# con_IMU.net
KiCad netlist of a schematic drawn in EAGLE
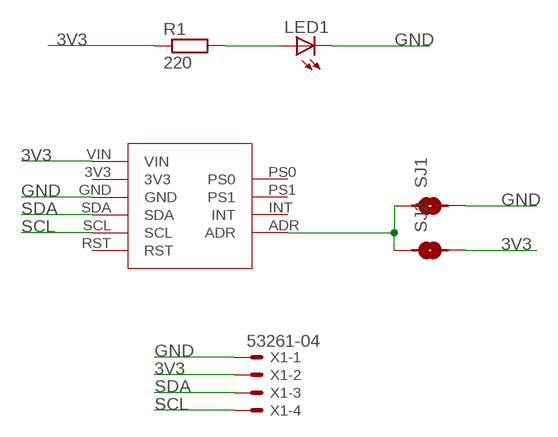
[diagram p0: schematic, sheet 1]

(export (version "E")
  (design (tool "Eeschema 10.0.6"))
  (components
    (comp (ref "LED1")
      (value "LEDCHIPLED_1206")
      (footprint "eagle-import:CHIPLED_1206")
      (libsource (lib "eagle-import") (part "LEDCHIPLED_1206"))
    )
    (comp (ref "R1")
      (value "220")
      (footprint "eagle-import:R1206")
      (libsource (lib "eagle-import") (part "RR1206"))
    )
    (comp (ref "SJ1")
      (value "SMD-JUMPER-2")
      (footprint "eagle-import:SMD-JUMPER-2")
      (libsource (lib "eagle-import") (part "SMD-JUMPER-2"))
    )
    (comp (ref "SJ2")
      (value "SMD-JUMPER-2")
      (footprint "eagle-import:SMD-JUMPER-2")
      (libsource (lib "eagle-import") (part "SMD-JUMPER-2"))
    )
    (comp (ref "U$1")
      (value "BNO055")
      (footprint "eagle-import:BNO055_MOD")
      (libsource (lib "eagle-import") (part "BNO055"))
    )
    (comp (ref "X1")
      (value "53261-04")
      (footprint "eagle-import:53261-04")
      (fields (field (name "MF") "MOLEX"))
      (libsource (lib "eagle-import") (part "53?-04261"))
    )
  )
  (nets
    (net (code "1") (name "/3V3") (class "Default")
      (node (ref "R1") (pin "1") (pinfunction "1_1") (pintype "passive"))
      (node (ref "SJ2") (pin "2") (pinfunction "2_2") (pintype "passive"))
      (node (ref "U$1") (pin "VIN") (pinfunction "VIN_VIN") (pintype "bidirectional"))
      (node (ref "X1") (pin "2") (pinfunction "S_2") (pintype "passive"))
    )
    (net (code "2") (name "/GND") (class "Default")
      (node (ref "LED1") (pin "C") (pinfunction "C_C") (pintype "passive"))
      (node (ref "SJ1") (pin "2") (pinfunction "2_2") (pintype "passive"))
      (node (ref "U$1") (pin "GND") (pinfunction "GND_GND") (pintype "bidirectional"))
      (node (ref "X1") (pin "1") (pinfunction "S_1") (pintype "passive"))
    )
    (net (code "3") (name "/SCL") (class "Default")
      (node (ref "U$1") (pin "SCL") (pinfunction "SCL_SCL") (pintype "bidirectional"))
      (node (ref "X1") (pin "4") (pinfunction "S_4") (pintype "passive"))
    )
    (net (code "4") (name "/SDA") (class "Default")
      (node (ref "U$1") (pin "SDA") (pinfunction "SDA_SDA") (pintype "bidirectional"))
      (node (ref "X1") (pin "3") (pinfunction "S_3") (pintype "passive"))
    )
    (net (code "5") (name "Net-(LED1-PadA)") (class "Default")
      (node (ref "LED1") (pin "A") (pinfunction "A_A") (pintype "passive"))
      (node (ref "R1") (pin "2") (pinfunction "2_2") (pintype "passive"))
    )
    (net (code "6") (name "Net-(SJ1-Pad1)") (class "Default")
      (node (ref "SJ1") (pin "1") (pinfunction "1_1") (pintype "passive"))
      (node (ref "SJ2") (pin "1") (pinfunction "1_1") (pintype "passive"))
      (node (ref "U$1") (pin "ADR") (pinfunction "ADR_ADR") (pintype "bidirectional"))
    )
    (net (code "7") (name "unconnected-(U$1-Pad3V3)") (class "Default")
      (node (ref "U$1") (pin "3V3") (pinfunction "3V3_3V3") (pintype "bidirectional"))
    )
    (net (code "8") (name "unconnected-(U$1-PadINT)") (class "Default")
      (node (ref "U$1") (pin "INT") (pinfunction "INT_INT") (pintype "bidirectional"))
    )
    (net (code "9") (name "unconnected-(U$1-PadPS0)") (class "Default")
      (node (ref "U$1") (pin "PS0") (pinfunction "PS0_PS0") (pintype "bidirectional"))
    )
    (net (code "10") (name "unconnected-(U$1-PadPS1)") (class "Default")
      (node (ref "U$1") (pin "PS1") (pinfunction "PS1_PS1") (pintype "bidirectional"))
    )
    (net (code "11") (name "unconnected-(U$1-PadRST)") (class "Default")
      (node (ref "U$1") (pin "RST") (pinfunction "RST_RST") (pintype "bidirectional"))
    )
  )
)
